# Sheet1.net
KiCad netlist of a schematic drawn in Altium Designer
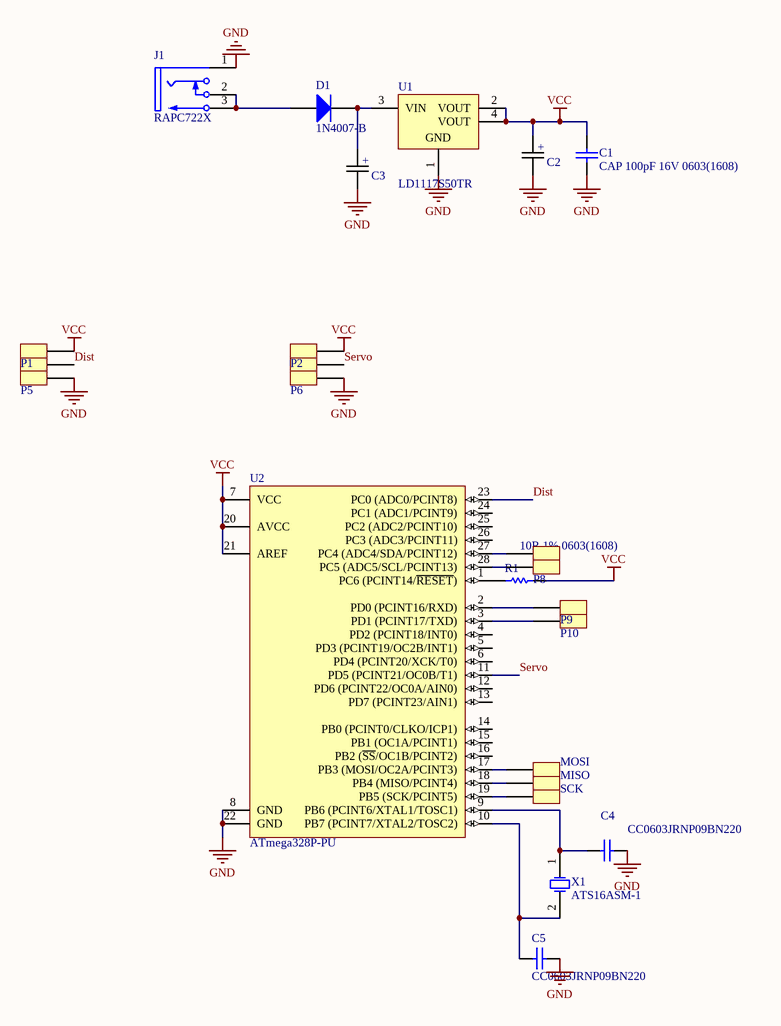
[diagram p0: Sheet1.SchDoc]

(export (version "E")
  (design (tool "Eeschema 10.0.6"))
  (components
    (comp (ref "C1")
      (value "CAP 100pF 16V 0603(1608)")
      (footprint "CAPC0603(1608)100_L")
      (description "CAP 100pF 16V ±5% 0603 (1608 Metric) Thickness 1mm SMD")
      (fields (field (name "TOLERANCE") "Â±5%"))
      (libsource (lib "Altium Content Vault") (part "CAP"))
    )
    (comp (ref "C2") (value "~") (footprint "CAP_EEFK_K16") (libsource (lib "SolarCar") (part "CAP")))
    (comp (ref "C3") (value "~") (footprint "CAP_EEFK_K16") (libsource (lib "SolarCar") (part "CAP")))
    (comp (ref "C4")
      (value "CC0603JRNP09BN220")
      (footprint "CAPC1608X90X40ML10T20")
      (description "Chip Capacitor, 22 pF, +/- 5%, 50 V, -55 to 125 degC, 0603 (1608 Metric), RoHS, Tape and Reel")
      (libsource (lib "Altium Content Vault") (part "CAP-NP-2"))
    )
    (comp (ref "C5")
      (value "CC0603JRNP09BN220")
      (footprint "CAPC1608X90X40ML10T20")
      (description "Chip Capacitor, 22 pF, +/- 5%, 50 V, -55 to 125 degC, 0603 (1608 Metric), RoHS, Tape and Reel")
      (libsource (lib "Altium Content Vault") (part "CAP-NP-2"))
    )
    (comp (ref "D1")
      (value "1N4007-B")
      (footprint "DIOD-DO-41-P-2_V")
      (description "1.0 A Rectifier, 8 pF, 1000 V, -65 to 150 degC, 2-Pin DO-41 Plastic, RoHS, Bulk")
      (fields (field (name "MANUFACTURER") "Diodes Inc"))
      (libsource (lib "Altium Content Vault") (part "DIOD-D-A1K2-2"))
    )
    (comp (ref "J1")
      (value "RAPC722X")
      (footprint "SWITCH-RAPC712X-3_V")
      (description "Power Jack, 5 A, 3-Pin THD, RoHS, Bulk")
      (fields (field (name "MANUFACTURER") "Switchcraft"))
      (libsource (lib "Altium Content Vault") (part "SWITCH-RAPC712X-3"))
    )
    (comp (ref "MISO") (value "Pin 100mil") (footprint "Pin 100mil") (libsource (lib "") (part "1-Pin_1")))
    (comp (ref "MOSI") (value "Pin 100mil") (footprint "Pin 100mil") (libsource (lib "") (part "1-Pin_1")))
    (comp (ref "P1")
      (value "Pin 100mil")
      (footprint "Pin 100mil")
      (libsource (lib "SolarCar") (part "1-Pin"))
    )
    (comp (ref "P2")
      (value "Pin 100mil")
      (footprint "Pin 100mil")
      (libsource (lib "SolarCar") (part "1-Pin"))
    )
    (comp (ref "P3")
      (value "Pin 100mil")
      (footprint "Pin 100mil")
      (libsource (lib "SolarCar") (part "1-Pin"))
    )
    (comp (ref "P4")
      (value "Pin 100mil")
      (footprint "Pin 100mil")
      (libsource (lib "SolarCar") (part "1-Pin"))
    )
    (comp (ref "P5")
      (value "Pin 100mil")
      (footprint "Pin 100mil")
      (libsource (lib "SolarCar") (part "1-Pin"))
    )
    (comp (ref "P6")
      (value "Pin 100mil")
      (footprint "Pin 100mil")
      (libsource (lib "SolarCar") (part "1-Pin"))
    )
    (comp (ref "P7") (value "Pin 100mil") (footprint "Pin 100mil") (libsource (lib "") (part "1-Pin_1")))
    (comp (ref "P8") (value "Pin 100mil") (footprint "Pin 100mil") (libsource (lib "") (part "1-Pin_1")))
    (comp (ref "P9") (value "Pin 100mil") (footprint "Pin 100mil") (libsource (lib "") (part "1-Pin_1")))
    (comp (ref "P10") (value "Pin 100mil") (footprint "Pin 100mil") (libsource (lib "") (part "1-Pin_1")))
    (comp (ref "R1")
      (value "10R 1% 0603(1608)")
      (footprint "RESC0603(1608)_L")
      (description "10R 0.1W 1% 0603 (1608 Metric)  SMD")
      (fields (field (name "TOLERANCE") "1 %") (field (name "POWER") "0.1 W"))
      (libsource (lib "Altium Content Vault") (part "RES"))
    )
    (comp (ref "SCK") (value "Pin 100mil") (footprint "Pin 100mil") (libsource (lib "") (part "1-Pin_1")))
    (comp (ref "U1")
      (value "LD1117S50TR")
      (footprint "SOT-223_L")
      (description "Fixed Low Drop Positive Voltage Regulator, 5V, 4-Pin SOT-223, Tape and Reel")
      (libsource (lib "Altium Content Vault") (part "PM-REG-LD1117-SOT4"))
    )
    (comp (ref "U2")
      (value "ATmega328P-PU")
      (footprint "28P3")
      (libsource (lib "Altium Content Vault") (part "MC-8B-ATM48-IL28"))
    )
    (comp (ref "X1")
      (value "ATS16ASM-1")
      (footprint "CTS-ATS-SM-XTAL-2")
      (description "ATS-SM Series Quartz Crystal, 16 MHz, -20 to 70 degC, 11.1 x 4.83 x 4.3mm SMD, RoHS, Tape and Reel")
      (fields (field (name "MANUFACTURER") "CTS Corporation"))
      (libsource (lib "Altium Content Vault") (part "CTS-ATS-SM-XTAL-2"))
    )
  )
  (nets
    (net (code "1") (name "/Dist") (class "Default")
      (node (ref "P3") (pin "0") (pinfunction "0_0") (pintype "passive"))
      (node (ref "U2") (pin "23") (pinfunction "PC0_(ADC0/PCINT8)_23") (pintype "bidirectional"))
    )
    (net (code "2") (name "/Servo") (class "Default")
      (node (ref "P4") (pin "0") (pinfunction "0_0") (pintype "passive"))
      (node (ref "U2") (pin "11") (pinfunction "PD5_(PCINT21/OC0B/T1)_11") (pintype "bidirectional"))
    )
    (net (code "3") (name "GND") (class "Default")
      (node (ref "C1") (pin "1") (pinfunction "1_1") (pintype "passive"))
      (node (ref "C2") (pin "-") (pinfunction "-_-") (pintype "power_in"))
      (node (ref "C3") (pin "-") (pinfunction "-_-") (pintype "power_in"))
      (node (ref "C4") (pin "2") (pinfunction "2_2") (pintype "passive"))
      (node (ref "C5") (pin "2") (pinfunction "2_2") (pintype "passive"))
      (node (ref "J1") (pin "1") (pinfunction "1_1") (pintype "passive"))
      (node (ref "P5") (pin "0") (pinfunction "0_0") (pintype "passive"))
      (node (ref "P6") (pin "0") (pinfunction "0_0") (pintype "passive"))
      (node (ref "U1") (pin "1") (pinfunction "GND_1") (pintype "power_in"))
      (node (ref "U2") (pin "22") (pinfunction "GND_22") (pintype "power_in"))
      (node (ref "U2") (pin "8") (pinfunction "GND_8") (pintype "power_in"))
    )
    (net (code "4") (name "Net-(D1-A)") (class "Default")
      (node (ref "D1") (pin "1") (pinfunction "A_1") (pintype "passive"))
      (node (ref "J1") (pin "2") (pinfunction "2_2") (pintype "passive"))
      (node (ref "J1") (pin "3") (pinfunction "3_3") (pintype "passive"))
    )
    (net (code "5") (name "Net-(D1-K)") (class "Default")
      (node (ref "C3") (pin "+") (pinfunction "+_+") (pintype "power_in"))
      (node (ref "D1") (pin "2") (pinfunction "K_2") (pintype "passive"))
      (node (ref "U1") (pin "3") (pinfunction "VIN_3") (pintype "power_in"))
    )
    (net (code "6") (name "Net-(U2-PB3_(MOSI{slash}OC2A{slash}PCINT3))") (class "Default")
      (node (ref "MOSI") (pin "0") (pinfunction "0_0") (pintype "passive"))
      (node (ref "U2") (pin "17") (pinfunction "PB3_(MOSI/OC2A/PCINT3)_17") (pintype "bidirectional"))
    )
    (net (code "7") (name "Net-(U2-PB4_(MISO{slash}PCINT4))") (class "Default")
      (node (ref "MISO") (pin "0") (pinfunction "0_0") (pintype "passive"))
      (node (ref "U2") (pin "18") (pinfunction "PB4_(MISO/PCINT4)_18") (pintype "bidirectional"))
    )
    (net (code "8") (name "Net-(U2-PB5_(SCK{slash}PCINT5))") (class "Default")
      (node (ref "SCK") (pin "0") (pinfunction "0_0") (pintype "passive"))
      (node (ref "U2") (pin "19") (pinfunction "PB5_(SCK/PCINT5)_19") (pintype "bidirectional"))
    )
    (net (code "9") (name "Net-(U2-PB6_(PCINT6{slash}XTAL1{slash}TOSC1))") (class "Default")
      (node (ref "C4") (pin "1") (pinfunction "1_1") (pintype "passive"))
      (node (ref "U2") (pin "9") (pinfunction "PB6_(PCINT6/XTAL1/TOSC1)_9") (pintype "bidirectional"))
      (node (ref "X1") (pin "1") (pinfunction "X1_1") (pintype "passive"))
    )
    (net (code "10") (name "Net-(U2-PB7_(PCINT7{slash}XTAL2{slash}TOSC2))") (class "Default")
      (node (ref "C5") (pin "1") (pinfunction "1_1") (pintype "passive"))
      (node (ref "U2") (pin "10") (pinfunction "PB7_(PCINT7/XTAL2/TOSC2)_10") (pintype "bidirectional"))
      (node (ref "X1") (pin "2") (pinfunction "X2_2") (pintype "passive"))
    )
    (net (code "11") (name "Net-(U2-PC4_(ADC4{slash}SDA{slash}PCINT12))") (class "Default")
      (node (ref "P7") (pin "0") (pinfunction "0_0") (pintype "passive"))
      (node (ref "U2") (pin "27") (pinfunction "PC4_(ADC4/SDA/PCINT12)_27") (pintype "bidirectional"))
    )
    (net (code "12") (name "Net-(U2-PC5_(ADC5{slash}SCL{slash}PCINT13))") (class "Default")
      (node (ref "P8") (pin "0") (pinfunction "0_0") (pintype "passive"))
      (node (ref "U2") (pin "28") (pinfunction "PC5_(ADC5/SCL/PCINT13)_28") (pintype "bidirectional"))
    )
    (net (code "13") (name "Net-(U2-PC6_(PCINT14{slash}~{RESET}))") (class "Default")
      (node (ref "R1") (pin "1") (pinfunction "1_1") (pintype "passive"))
      (node (ref "U2") (pin "1") (pinfunction "PC6_(PCINT14/~{RESET})_1") (pintype "bidirectional"))
    )
    (net (code "14") (name "Net-(U2-PD0_(PCINT16{slash}RXD))") (class "Default")
      (node (ref "P9") (pin "0") (pinfunction "0_0") (pintype "passive"))
      (node (ref "U2") (pin "2") (pinfunction "PD0_(PCINT16/RXD)_2") (pintype "bidirectional"))
    )
    (net (code "15") (name "Net-(U2-PD1_(PCINT17{slash}TXD))") (class "Default")
      (node (ref "P10") (pin "0") (pinfunction "0_0") (pintype "passive"))
      (node (ref "U2") (pin "3") (pinfunction "PD1_(PCINT17/TXD)_3") (pintype "bidirectional"))
    )
    (net (code "16") (name "VCC") (class "Default")
      (node (ref "C1") (pin "2") (pinfunction "2_2") (pintype "passive"))
      (node (ref "C2") (pin "+") (pinfunction "+_+") (pintype "power_in"))
      (node (ref "P1") (pin "0") (pinfunction "0_0") (pintype "passive"))
      (node (ref "P2") (pin "0") (pinfunction "0_0") (pintype "passive"))
      (node (ref "R1") (pin "2") (pinfunction "2_2") (pintype "passive"))
      (node (ref "U1") (pin "2") (pinfunction "VOUT_2") (pintype "power_in"))
      (node (ref "U1") (pin "4") (pinfunction "VOUT_4") (pintype "power_in"))
      (node (ref "U2") (pin "20") (pinfunction "AVCC_20") (pintype "power_in"))
      (node (ref "U2") (pin "21") (pinfunction "AREF_21") (pintype "power_in"))
      (node (ref "U2") (pin "7") (pinfunction "VCC_7") (pintype "power_in"))
    )
    (net (code "17") (name "unconnected-(U2-PB0_(PCINT0{slash}CLKO{slash}ICP1)-Pad14)") (class "Default")
      (node (ref "U2") (pin "14") (pinfunction "PB0_(PCINT0/CLKO/ICP1)_14") (pintype "bidirectional"))
    )
    (net (code "18") (name "unconnected-(U2-PB1_(OC1A{slash}PCINT1)-Pad15)") (class "Default")
      (node (ref "U2") (pin "15") (pinfunction "PB1_(OC1A/PCINT1)_15") (pintype "bidirectional"))
    )
    (net (code "19") (name "unconnected-(U2-PB2_(~{SS}{slash}OC1B{slash}PCINT2)-Pad16)") (class "Default")
      (node (ref "U2") (pin "16") (pinfunction "PB2_(~{SS}/OC1B/PCINT2)_16") (pintype "bidirectional"))
    )
    (net (code "20") (name "unconnected-(U2-PC1_(ADC1{slash}PCINT9)-Pad24)") (class "Default")
      (node (ref "U2") (pin "24") (pinfunction "PC1_(ADC1/PCINT9)_24") (pintype "bidirectional"))
    )
    (net (code "21") (name "unconnected-(U2-PC2_(ADC2{slash}PCINT10)-Pad25)") (class "Default")
      (node (ref "U2") (pin "25") (pinfunction "PC2_(ADC2/PCINT10)_25") (pintype "bidirectional"))
    )
    (net (code "22") (name "unconnected-(U2-PC3_(ADC3{slash}PCINT11)-Pad26)") (class "Default")
      (node (ref "U2") (pin "26") (pinfunction "PC3_(ADC3/PCINT11)_26") (pintype "bidirectional"))
    )
    (net (code "23") (name "unconnected-(U2-PD2_(PCINT18{slash}INT0)-Pad4)") (class "Default")
      (node (ref "U2") (pin "4") (pinfunction "PD2_(PCINT18/INT0)_4") (pintype "bidirectional"))
    )
    (net (code "24") (name "unconnected-(U2-PD3_(PCINT19{slash}OC2B{slash}INT1)-Pad5)") (class "Default")
      (node (ref "U2") (pin "5") (pinfunction "PD3_(PCINT19/OC2B/INT1)_5") (pintype "bidirectional"))
    )
    (net (code "25") (name "unconnected-(U2-PD4_(PCINT20{slash}XCK{slash}T0)-Pad6)") (class "Default")
      (node (ref "U2") (pin "6") (pinfunction "PD4_(PCINT20/XCK/T0)_6") (pintype "bidirectional"))
    )
    (net (code "26") (name "unconnected-(U2-PD6_(PCINT22{slash}OC0A{slash}AIN0)-Pad12)") (class "Default")
      (node (ref "U2") (pin "12") (pinfunction "PD6_(PCINT22/OC0A/AIN0)_12") (pintype "bidirectional"))
    )
    (net (code "27") (name "unconnected-(U2-PD7_(PCINT23{slash}AIN1)-Pad13)") (class "Default")
      (node (ref "U2") (pin "13") (pinfunction "PD7_(PCINT23/AIN1)_13") (pintype "bidirectional"))
    )
  )
)
